# design.net
KiCad netlist of a schematic drawn in Altium Designer
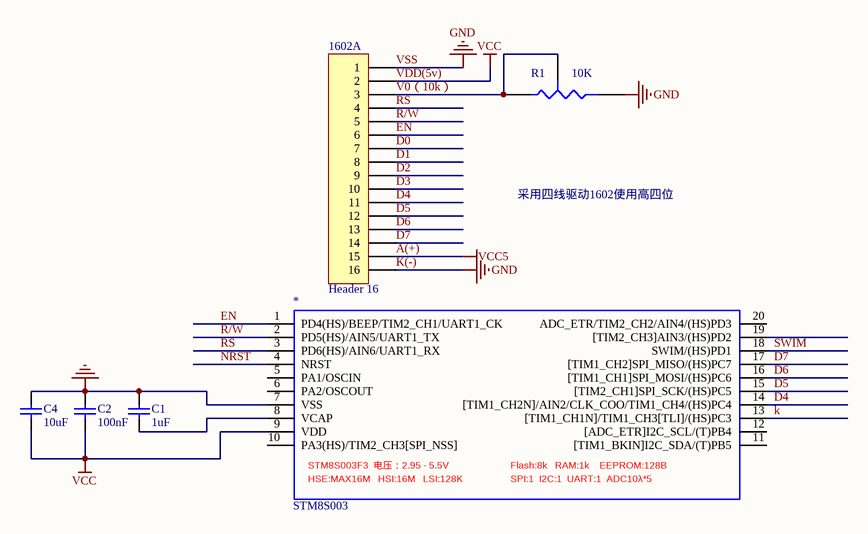
[diagram p0: 脉冲延时.SchDoc]

(export (version "E")
  (design (tool "Eeschema 10.0.6"))
  (components
    (comp (ref "*") (value "STM8S003") (libsource (lib "STM原理图") (part "STM8S003")))
    (comp (ref "1602A")
      (value "Header 16")
      (footprint "HDR1X16")
      (description "Header, 16-Pin")
      (fields (field (name "PUBLISHER") "Altium Limited"))
      (libsource (lib "Miscellaneous Connectors") (part "Header 16"))
    )
    (comp (ref "C1")
      (value "1uF")
      (footprint "0603C")
      (description "Capacitor")
      (fields (field (name "PUBLISHER") "Altium Limited"))
      (libsource (lib "Miscellaneous Devices") (part "Cap"))
    )
    (comp (ref "C2")
      (value "100nF")
      (footprint "0603C")
      (description "Capacitor")
      (fields (field (name "PUBLISHER") "Altium Limited"))
      (libsource (lib "Miscellaneous Devices") (part "Cap"))
    )
    (comp (ref "C4")
      (value "10uF")
      (footprint "0603C")
      (description "Capacitor")
      (fields (field (name "PUBLISHER") "Altium Limited"))
      (libsource (lib "Miscellaneous Devices") (part "Cap"))
    )
    (comp (ref "R1")
      (value "10K")
      (footprint "VR3")
      (description "Tapped Resistor")
      (fields (field (name "Comment") "Res Tap") (field (name "PUBLISHER") "Altium Limited"))
      (libsource (lib "Miscellaneous Devices") (part "Res Tap"))
    )
  )
  (nets
    (net (code "1") (name "/D0") (class "Default")
      (node (ref "1602A") (pin "7") (pinfunction "7_7") (pintype "passive"))
    )
    (net (code "2") (name "/D1") (class "Default")
      (node (ref "1602A") (pin "8") (pinfunction "8_8") (pintype "passive"))
    )
    (net (code "3") (name "/D2") (class "Default")
      (node (ref "1602A") (pin "9") (pinfunction "9_9") (pintype "passive"))
    )
    (net (code "4") (name "/D3") (class "Default")
      (node (ref "1602A") (pin "10") (pinfunction "10_10") (pintype "passive"))
    )
    (net (code "5") (name "/D4") (class "Default")
      (node (ref "*") (pin "14") (pinfunction "[TIM1_CH2N]/AIN2/CLK_COO/TIM1_CH4/(HS)PC4_14") (pintype "passive"))
      (node (ref "1602A") (pin "11") (pinfunction "11_11") (pintype "passive"))
    )
    (net (code "6") (name "/D5") (class "Default")
      (node (ref "*") (pin "15") (pinfunction "[TIM2_CH1]SPI_SCK/(HS)PC5_15") (pintype "passive"))
      (node (ref "1602A") (pin "12") (pinfunction "12_12") (pintype "passive"))
    )
    (net (code "7") (name "/D6") (class "Default")
      (node (ref "*") (pin "16") (pinfunction "[TIM1_CH1]SPI_MOSI/(HS)PC6_16") (pintype "passive"))
      (node (ref "1602A") (pin "13") (pinfunction "13_13") (pintype "passive"))
    )
    (net (code "8") (name "/D7") (class "Default")
      (node (ref "*") (pin "17") (pinfunction "[TIM1_CH2]SPI_MISO/(HS)PC7_17") (pintype "passive"))
      (node (ref "1602A") (pin "14") (pinfunction "14_14") (pintype "passive"))
    )
    (net (code "9") (name "/EN") (class "Default")
      (node (ref "*") (pin "1") (pinfunction "PD4(HS)/BEEP/TIM2_CH1/UART1_CK_1") (pintype "passive"))
      (node (ref "1602A") (pin "6") (pinfunction "6_6") (pintype "passive"))
    )
    (net (code "10") (name "/NRST") (class "Default")
      (node (ref "*") (pin "4") (pinfunction "NRST_4") (pintype "passive"))
    )
    (net (code "11") (name "/RS") (class "Default")
      (node (ref "*") (pin "3") (pinfunction "PD6(HS)/AIN6/UART1_RX_3") (pintype "passive"))
      (node (ref "1602A") (pin "4") (pinfunction "4_4") (pintype "passive"))
    )
    (net (code "12") (name "/R{slash}W") (class "Default")
      (node (ref "*") (pin "2") (pinfunction "PD5(HS)/AIN5/UART1_TX_2") (pintype "passive"))
      (node (ref "1602A") (pin "5") (pinfunction "5_5") (pintype "passive"))
    )
    (net (code "13") (name "/SWIM") (class "Default")
      (node (ref "*") (pin "18") (pinfunction "SWIM/(HS)PD1_18") (pintype "passive"))
    )
    (net (code "14") (name "/V0（10k）") (class "Default")
      (node (ref "1602A") (pin "3") (pinfunction "3_3") (pintype "passive"))
      (node (ref "R1") (pin "1") (pinfunction "A_1") (pintype "passive"))
      (node (ref "R1") (pin "3") (pinfunction "TAP_3") (pintype "passive"))
    )
    (net (code "15") (name "/k") (class "Default")
      (node (ref "*") (pin "13") (pinfunction "[TIM1_CH1N]/TIM1_CH3[TLI]/(HS)PC3_13") (pintype "passive"))
    )
    (net (code "16") (name "GND") (class "Default")
      (node (ref "*") (pin "7") (pinfunction "VSS_7") (pintype "passive"))
      (node (ref "1602A") (pin "1") (pinfunction "1_1") (pintype "passive"))
      (node (ref "1602A") (pin "16") (pinfunction "16_16") (pintype "passive"))
      (node (ref "C1") (pin "2") (pinfunction "2_2") (pintype "passive"))
      (node (ref "C2") (pin "2") (pinfunction "2_2") (pintype "passive"))
      (node (ref "C4") (pin "2") (pinfunction "2_2") (pintype "passive"))
      (node (ref "R1") (pin "2") (pinfunction "B_2") (pintype "passive"))
    )
    (net (code "17") (name "Net-(*-VCAP)") (class "Default")
      (node (ref "*") (pin "8") (pinfunction "VCAP_8") (pintype "passive"))
      (node (ref "C1") (pin "1") (pinfunction "1_1") (pintype "passive"))
    )
    (net (code "18") (name "VCC") (class "Default")
      (node (ref "*") (pin "9") (pinfunction "VDD_9") (pintype "passive"))
      (node (ref "1602A") (pin "2") (pinfunction "2_2") (pintype "passive"))
      (node (ref "C2") (pin "1") (pinfunction "1_1") (pintype "passive"))
      (node (ref "C4") (pin "1") (pinfunction "1_1") (pintype "passive"))
    )
    (net (code "19") (name "VCC5") (class "Default")
      (node (ref "1602A") (pin "15") (pinfunction "15_15") (pintype "passive"))
    )
    (net (code "20") (name "unconnected-(*-ADC_ETR{slash}TIM2_CH2{slash}AIN4{slash}(HS)PD3-Pad20)") (class "Default")
      (node (ref "*") (pin "20") (pinfunction "ADC_ETR/TIM2_CH2/AIN4/(HS)PD3_20") (pintype "passive"))
    )
    (net (code "21") (name "unconnected-(*-PA1{slash}OSCIN-Pad5)") (class "Default")
      (node (ref "*") (pin "5") (pinfunction "PA1/OSCIN_5") (pintype "passive"))
    )
    (net (code "22") (name "unconnected-(*-PA2{slash}OSCOUT-Pad6)") (class "Default")
      (node (ref "*") (pin "6") (pinfunction "PA2/OSCOUT_6") (pintype "passive"))
    )
    (net (code "23") (name "unconnected-(*-PA3(HS){slash}TIM2_CH3[SPI_NSS]-Pad10)") (class "Default")
      (node (ref "*") (pin "10") (pinfunction "PA3(HS)/TIM2_CH3[SPI_NSS]_10") (pintype "passive"))
    )
    (net (code "24") (name "unconnected-(*-[ADC_ETR]I2C_SCL{slash}(T)PB4-Pad12)") (class "Default")
      (node (ref "*") (pin "12") (pinfunction "[ADC_ETR]I2C_SCL/(T)PB4_12") (pintype "passive"))
    )
    (net (code "25") (name "unconnected-(*-[TIM1_BKIN]I2C_SDA{slash}(T)PB5-Pad11)") (class "Default")
      (node (ref "*") (pin "11") (pinfunction "[TIM1_BKIN]I2C_SDA/(T)PB5_11") (pintype "passive"))
    )
    (net (code "26") (name "unconnected-(*-[TIM2_CH3]AIN3{slash}(HS)PD2-Pad19)") (class "Default")
      (node (ref "*") (pin "19") (pinfunction "[TIM2_CH3]AIN3/(HS)PD2_19") (pintype "passive"))
    )
  )
)
